# controller.net
KiCad netlist of a schematic drawn in EAGLE
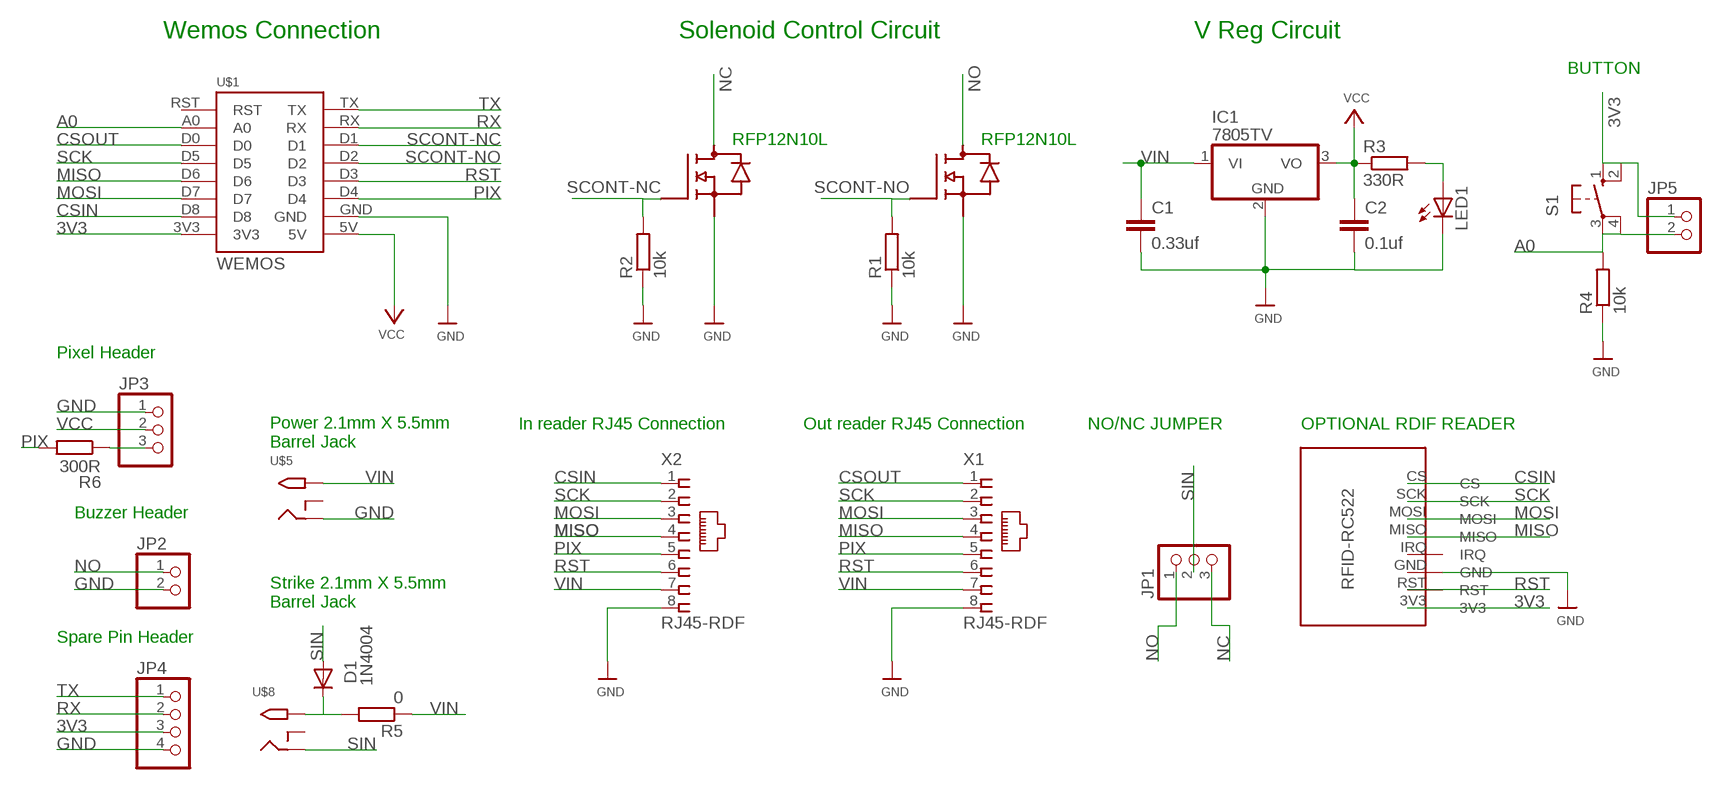
[diagram p0: schematic, sheet 1]

(export (version "E")
  (design (tool "Eeschema 10.0.6"))
  (components
    (comp (ref "C1")
      (value "0.33uf")
      (footprint "eagle-import:C050-024X044")
      (libsource (lib "eagle-import") (part "C-EU050-024X044"))
    )
    (comp (ref "C2")
      (value "0.1uf")
      (footprint "eagle-import:C050-024X044")
      (libsource (lib "eagle-import") (part "C-EU050-024X044"))
    )
    (comp (ref "D1")
      (value "1N4004")
      (footprint "eagle-import:DO41-10")
      (libsource (lib "eagle-import") (part "1N4004"))
    )
    (comp (ref "IC1")
      (value "7805TV")
      (footprint "eagle-import:TO220V")
      (libsource (lib "eagle-import") (part "78TV05"))
    )
    (comp (ref "IC2")
      (value "NTD4963NT0220")
      (footprint "eagle-import:T0220")
      (libsource (lib "eagle-import") (part "NTD4963NT0220"))
    )
    (comp (ref "IC3")
      (value "NTD4963NT0220")
      (footprint "eagle-import:T0220")
      (libsource (lib "eagle-import") (part "NTD4963NT0220"))
    )
    (comp (ref "JP1")
      (value "PINHD-1X3CB")
      (footprint "eagle-import:1X03-CLEANBIG")
      (libsource (lib "eagle-import") (part "PINHD-1X3CB"))
    )
    (comp (ref "JP2")
      (value "PINHD-1X2")
      (footprint "eagle-import:1X02")
      (libsource (lib "eagle-import") (part "PINHD-1X2"))
    )
    (comp (ref "JP3")
      (value "PINHD-1X3CB")
      (footprint "eagle-import:1X03-CLEANBIG")
      (libsource (lib "eagle-import") (part "PINHD-1X3CB"))
    )
    (comp (ref "JP4")
      (value "PINHD-1X4")
      (footprint "eagle-import:1X04")
      (libsource (lib "eagle-import") (part "PINHD-1X4"))
    )
    (comp (ref "JP5")
      (value "PINHD-1X2")
      (footprint "eagle-import:1X02")
      (libsource (lib "eagle-import") (part "PINHD-1X2"))
    )
    (comp (ref "LED1")
      (value "LED3MM")
      (footprint "eagle-import:LED3MM")
      (libsource (lib "eagle-import") (part "LED3MM"))
    )
    (comp (ref "R1")
      (value "10k")
      (footprint "eagle-import:0204_5")
      (libsource (lib "eagle-import") (part "R-EU_0204/5"))
    )
    (comp (ref "R2")
      (value "10k")
      (footprint "eagle-import:0204_5")
      (libsource (lib "eagle-import") (part "R-EU_0204/5"))
    )
    (comp (ref "R3")
      (value "330R")
      (footprint "eagle-import:0204_5")
      (libsource (lib "eagle-import") (part "R-EU_0204/5"))
    )
    (comp (ref "R4")
      (value "10k")
      (footprint "eagle-import:0204_5")
      (libsource (lib "eagle-import") (part "R-EU_0204/5"))
    )
    (comp (ref "R5")
      (value "0")
      (footprint "eagle-import:0204_5")
      (libsource (lib "eagle-import") (part "R-EU_0204/5"))
    )
    (comp (ref "R6")
      (value "300R")
      (footprint "eagle-import:0204_5")
      (libsource (lib "eagle-import") (part "R-EU_0204/5"))
    )
    (comp (ref "S1")
      (value "10-XX")
      (footprint "eagle-import:B3F-10XX")
      (fields (field (name "MPN") "B3F-1000"))
      (libsource (lib "eagle-import") (part "10-XX"))
    )
    (comp (ref "U$1")
      (value "WEMOS")
      (footprint "eagle-import:WEMOS")
      (libsource (lib "eagle-import") (part "WEMOS"))
    )
    (comp (ref "U$5")
      (value "2.1MMJACKTHM")
      (footprint "eagle-import:PJ-102A")
      (libsource (lib "eagle-import") (part "2.1MMJACKTHM"))
    )
    (comp (ref "U$8")
      (value "2.1MMJACKTHM")
      (footprint "eagle-import:PJ-102A")
      (libsource (lib "eagle-import") (part "2.1MMJACKTHM"))
    )
    (comp (ref "U$14")
      (value "RFID-RC522NOHOLES")
      (footprint "eagle-import:RFID-RC522-NOHOLES")
      (libsource (lib "eagle-import") (part "RFID-RC522NOHOLES"))
    )
    (comp (ref "X1")
      (value "RJ45-RDF")
      (footprint "eagle-import:RJ45-RDF")
      (libsource (lib "eagle-import") (part "RJ45-RDF"))
    )
    (comp (ref "X2")
      (value "RJ45-RDF")
      (footprint "eagle-import:RJ45-RDF")
      (libsource (lib "eagle-import") (part "RJ45-RDF"))
    )
  )
  (nets
    (net (code "1") (name "/3V3") (class "Default")
      (node (ref "JP4") (pin "3") (pinfunction "3_3") (pintype "passive"))
      (node (ref "JP5") (pin "1") (pinfunction "1_1") (pintype "passive"))
      (node (ref "S1") (pin "1") (pinfunction "S_1") (pintype "passive"))
      (node (ref "S1") (pin "2") (pinfunction "S1_2") (pintype "passive"))
      (node (ref "U$1") (pin "3V3") (pinfunction "3V3_3V3") (pintype "bidirectional"))
      (node (ref "U$14") (pin "3V3") (pinfunction "3V3_3V3") (pintype "bidirectional"))
    )
    (net (code "2") (name "/A0") (class "Default")
      (node (ref "JP5") (pin "2") (pinfunction "2_2") (pintype "passive"))
      (node (ref "R4") (pin "2") (pinfunction "2_2") (pintype "passive"))
      (node (ref "S1") (pin "3") (pinfunction "P_3") (pintype "passive"))
      (node (ref "S1") (pin "4") (pinfunction "P1_4") (pintype "passive"))
      (node (ref "U$1") (pin "A0") (pinfunction "A0_A0") (pintype "bidirectional"))
    )
    (net (code "3") (name "/CSIN") (class "Default")
      (node (ref "U$1") (pin "D8") (pinfunction "D8_D8") (pintype "bidirectional"))
      (node (ref "U$14") (pin "CS") (pinfunction "CS_CS") (pintype "bidirectional"))
      (node (ref "X2") (pin "1") (pinfunction "1_1") (pintype "passive"))
    )
    (net (code "4") (name "/CSOUT") (class "Default")
      (node (ref "U$1") (pin "D0") (pinfunction "D0_D0") (pintype "bidirectional"))
      (node (ref "X1") (pin "1") (pinfunction "1_1") (pintype "passive"))
    )
    (net (code "5") (name "/MISO") (class "Default")
      (node (ref "U$1") (pin "D6") (pinfunction "D6_D6") (pintype "bidirectional"))
      (node (ref "U$14") (pin "MISO") (pinfunction "MISO_MISO") (pintype "bidirectional"))
      (node (ref "X1") (pin "4") (pinfunction "4_4") (pintype "passive"))
      (node (ref "X2") (pin "4") (pinfunction "4_4") (pintype "passive"))
    )
    (net (code "6") (name "/MOSI") (class "Default")
      (node (ref "U$1") (pin "D7") (pinfunction "D7_D7") (pintype "bidirectional"))
      (node (ref "U$14") (pin "MOSI") (pinfunction "MOSI_MOSI") (pintype "bidirectional"))
      (node (ref "X1") (pin "3") (pinfunction "3_3") (pintype "passive"))
      (node (ref "X2") (pin "3") (pinfunction "3_3") (pintype "passive"))
    )
    (net (code "7") (name "/NC") (class "Default")
      (node (ref "IC2") (pin "2") (pinfunction "D_2") (pintype "passive"))
      (node (ref "JP1") (pin "3") (pinfunction "3_3") (pintype "passive"))
    )
    (net (code "8") (name "/NO") (class "Default")
      (node (ref "IC3") (pin "2") (pinfunction "D_2") (pintype "passive"))
      (node (ref "JP1") (pin "1") (pinfunction "1_1") (pintype "passive"))
      (node (ref "JP2") (pin "1") (pinfunction "1_1") (pintype "passive"))
    )
    (net (code "9") (name "/PIX") (class "Default")
      (node (ref "R6") (pin "2") (pinfunction "2_2") (pintype "passive"))
      (node (ref "U$1") (pin "D4") (pinfunction "D4_D4") (pintype "bidirectional"))
      (node (ref "X1") (pin "5") (pinfunction "5_5") (pintype "passive"))
      (node (ref "X2") (pin "5") (pinfunction "5_5") (pintype "passive"))
    )
    (net (code "10") (name "/RST") (class "Default")
      (node (ref "U$1") (pin "D3") (pinfunction "D3_D3") (pintype "bidirectional"))
      (node (ref "U$14") (pin "RST") (pinfunction "RST_RST") (pintype "bidirectional"))
      (node (ref "X1") (pin "6") (pinfunction "6_6") (pintype "passive"))
      (node (ref "X2") (pin "6") (pinfunction "6_6") (pintype "passive"))
    )
    (net (code "11") (name "/RX") (class "Default")
      (node (ref "JP4") (pin "2") (pinfunction "2_2") (pintype "passive"))
      (node (ref "U$1") (pin "RX") (pinfunction "RX_RX") (pintype "bidirectional"))
    )
    (net (code "12") (name "/SCK") (class "Default")
      (node (ref "U$1") (pin "D5") (pinfunction "D5_D5") (pintype "bidirectional"))
      (node (ref "U$14") (pin "SCK") (pinfunction "SCK_SCK") (pintype "bidirectional"))
      (node (ref "X1") (pin "2") (pinfunction "2_2") (pintype "passive"))
      (node (ref "X2") (pin "2") (pinfunction "2_2") (pintype "passive"))
    )
    (net (code "13") (name "/SCONT-NC") (class "Default")
      (node (ref "IC2") (pin "1") (pinfunction "G_1") (pintype "passive"))
      (node (ref "R2") (pin "2") (pinfunction "2_2") (pintype "passive"))
      (node (ref "U$1") (pin "D1") (pinfunction "D1_D1") (pintype "bidirectional"))
    )
    (net (code "14") (name "/SCONT-NO") (class "Default")
      (node (ref "IC3") (pin "1") (pinfunction "G_1") (pintype "passive"))
      (node (ref "R1") (pin "2") (pinfunction "2_2") (pintype "passive"))
      (node (ref "U$1") (pin "D2") (pinfunction "D2_D2") (pintype "bidirectional"))
    )
    (net (code "15") (name "/SIN") (class "Default")
      (node (ref "D1") (pin "A") (pinfunction "A_A") (pintype "passive"))
      (node (ref "JP1") (pin "2") (pinfunction "2_2") (pintype "passive"))
      (node (ref "U$8") (pin "RING") (pinfunction "RING_RING") (pintype "bidirectional"))
    )
    (net (code "16") (name "/TX") (class "Default")
      (node (ref "JP4") (pin "1") (pinfunction "1_1") (pintype "passive"))
      (node (ref "U$1") (pin "TX") (pinfunction "TX_TX") (pintype "bidirectional"))
    )
    (net (code "17") (name "/VIN") (class "Default")
      (node (ref "C1") (pin "1") (pinfunction "1_1") (pintype "passive"))
      (node (ref "IC1") (pin "1") (pinfunction "VI_1") (pintype "input"))
      (node (ref "R5") (pin "1") (pinfunction "1_1") (pintype "passive"))
      (node (ref "U$5") (pin "TIP") (pinfunction "TIP_TIP") (pintype "bidirectional"))
      (node (ref "X1") (pin "7") (pinfunction "7_7") (pintype "passive"))
      (node (ref "X2") (pin "7") (pinfunction "7_7") (pintype "passive"))
    )
    (net (code "18") (name "GND") (class "Default")
      (node (ref "C1") (pin "2") (pinfunction "2_2") (pintype "passive"))
      (node (ref "C2") (pin "2") (pinfunction "2_2") (pintype "passive"))
      (node (ref "IC1") (pin "2") (pinfunction "GND_2") (pintype "passive"))
      (node (ref "IC2") (pin "3") (pinfunction "S_3") (pintype "passive"))
      (node (ref "IC3") (pin "3") (pinfunction "S_3") (pintype "passive"))
      (node (ref "JP2") (pin "2") (pinfunction "2_2") (pintype "passive"))
      (node (ref "JP3") (pin "1") (pinfunction "1_1") (pintype "passive"))
      (node (ref "JP4") (pin "4") (pinfunction "4_4") (pintype "passive"))
      (node (ref "LED1") (pin "K") (pinfunction "C_K") (pintype "passive"))
      (node (ref "R1") (pin "1") (pinfunction "1_1") (pintype "passive"))
      (node (ref "R2") (pin "1") (pinfunction "1_1") (pintype "passive"))
      (node (ref "R4") (pin "1") (pinfunction "1_1") (pintype "passive"))
      (node (ref "U$1") (pin "GND") (pinfunction "GND_GND") (pintype "bidirectional"))
      (node (ref "U$5") (pin "RING") (pinfunction "RING_RING") (pintype "bidirectional"))
      (node (ref "X1") (pin "8") (pinfunction "8_8") (pintype "passive"))
      (node (ref "X2") (pin "8") (pinfunction "8_8") (pintype "passive"))
    )
    (net (code "19") (name "Net-(D1-PadC)") (class "Default")
      (node (ref "D1") (pin "C") (pinfunction "C_C") (pintype "passive"))
      (node (ref "R5") (pin "2") (pinfunction "2_2") (pintype "passive"))
      (node (ref "U$8") (pin "TIP") (pinfunction "TIP_TIP") (pintype "bidirectional"))
    )
    (net (code "20") (name "Net-(JP3-Pad3)") (class "Default")
      (node (ref "JP3") (pin "3") (pinfunction "3_3") (pintype "passive"))
      (node (ref "R6") (pin "1") (pinfunction "1_1") (pintype "passive"))
    )
    (net (code "21") (name "Net-(LED1-PadA)") (class "Default")
      (node (ref "LED1") (pin "A") (pinfunction "A_A") (pintype "passive"))
      (node (ref "R3") (pin "2") (pinfunction "2_2") (pintype "passive"))
    )
    (net (code "22") (name "VCC") (class "Default")
      (node (ref "C2") (pin "1") (pinfunction "1_1") (pintype "passive"))
      (node (ref "IC1") (pin "3") (pinfunction "VO_3") (pintype "passive"))
      (node (ref "JP3") (pin "2") (pinfunction "2_2") (pintype "passive"))
      (node (ref "R3") (pin "1") (pinfunction "1_1") (pintype "passive"))
      (node (ref "U$1") (pin "5V") (pinfunction "5V_5V") (pintype "bidirectional"))
    )
    (net (code "23") (name "unconnected-(U$1-PadRST)") (class "Default")
      (node (ref "U$1") (pin "RST") (pinfunction "RST_RST") (pintype "bidirectional"))
    )
    (net (code "24") (name "unconnected-(U$5-PadRING_SW)") (class "Default")
      (node (ref "U$5") (pin "RING_SW") (pinfunction "RING_SW_RING_SW") (pintype "bidirectional"))
    )
    (net (code "25") (name "unconnected-(U$8-PadRING_SW)") (class "Default")
      (node (ref "U$8") (pin "RING_SW") (pinfunction "RING_SW_RING_SW") (pintype "bidirectional"))
    )
    (net (code "26") (name "unconnected-(U$14-PadGND)") (class "Default")
      (node (ref "U$14") (pin "GND") (pinfunction "GND_GND") (pintype "bidirectional"))
    )
    (net (code "27") (name "unconnected-(U$14-PadIRQ)") (class "Default")
      (node (ref "U$14") (pin "IRQ") (pinfunction "IRQ_IRQ") (pintype "bidirectional"))
    )
  )
)
